# Artemis_Dionysus_Connectors.net
KiCad netlist of a schematic drawn in Altium Designer
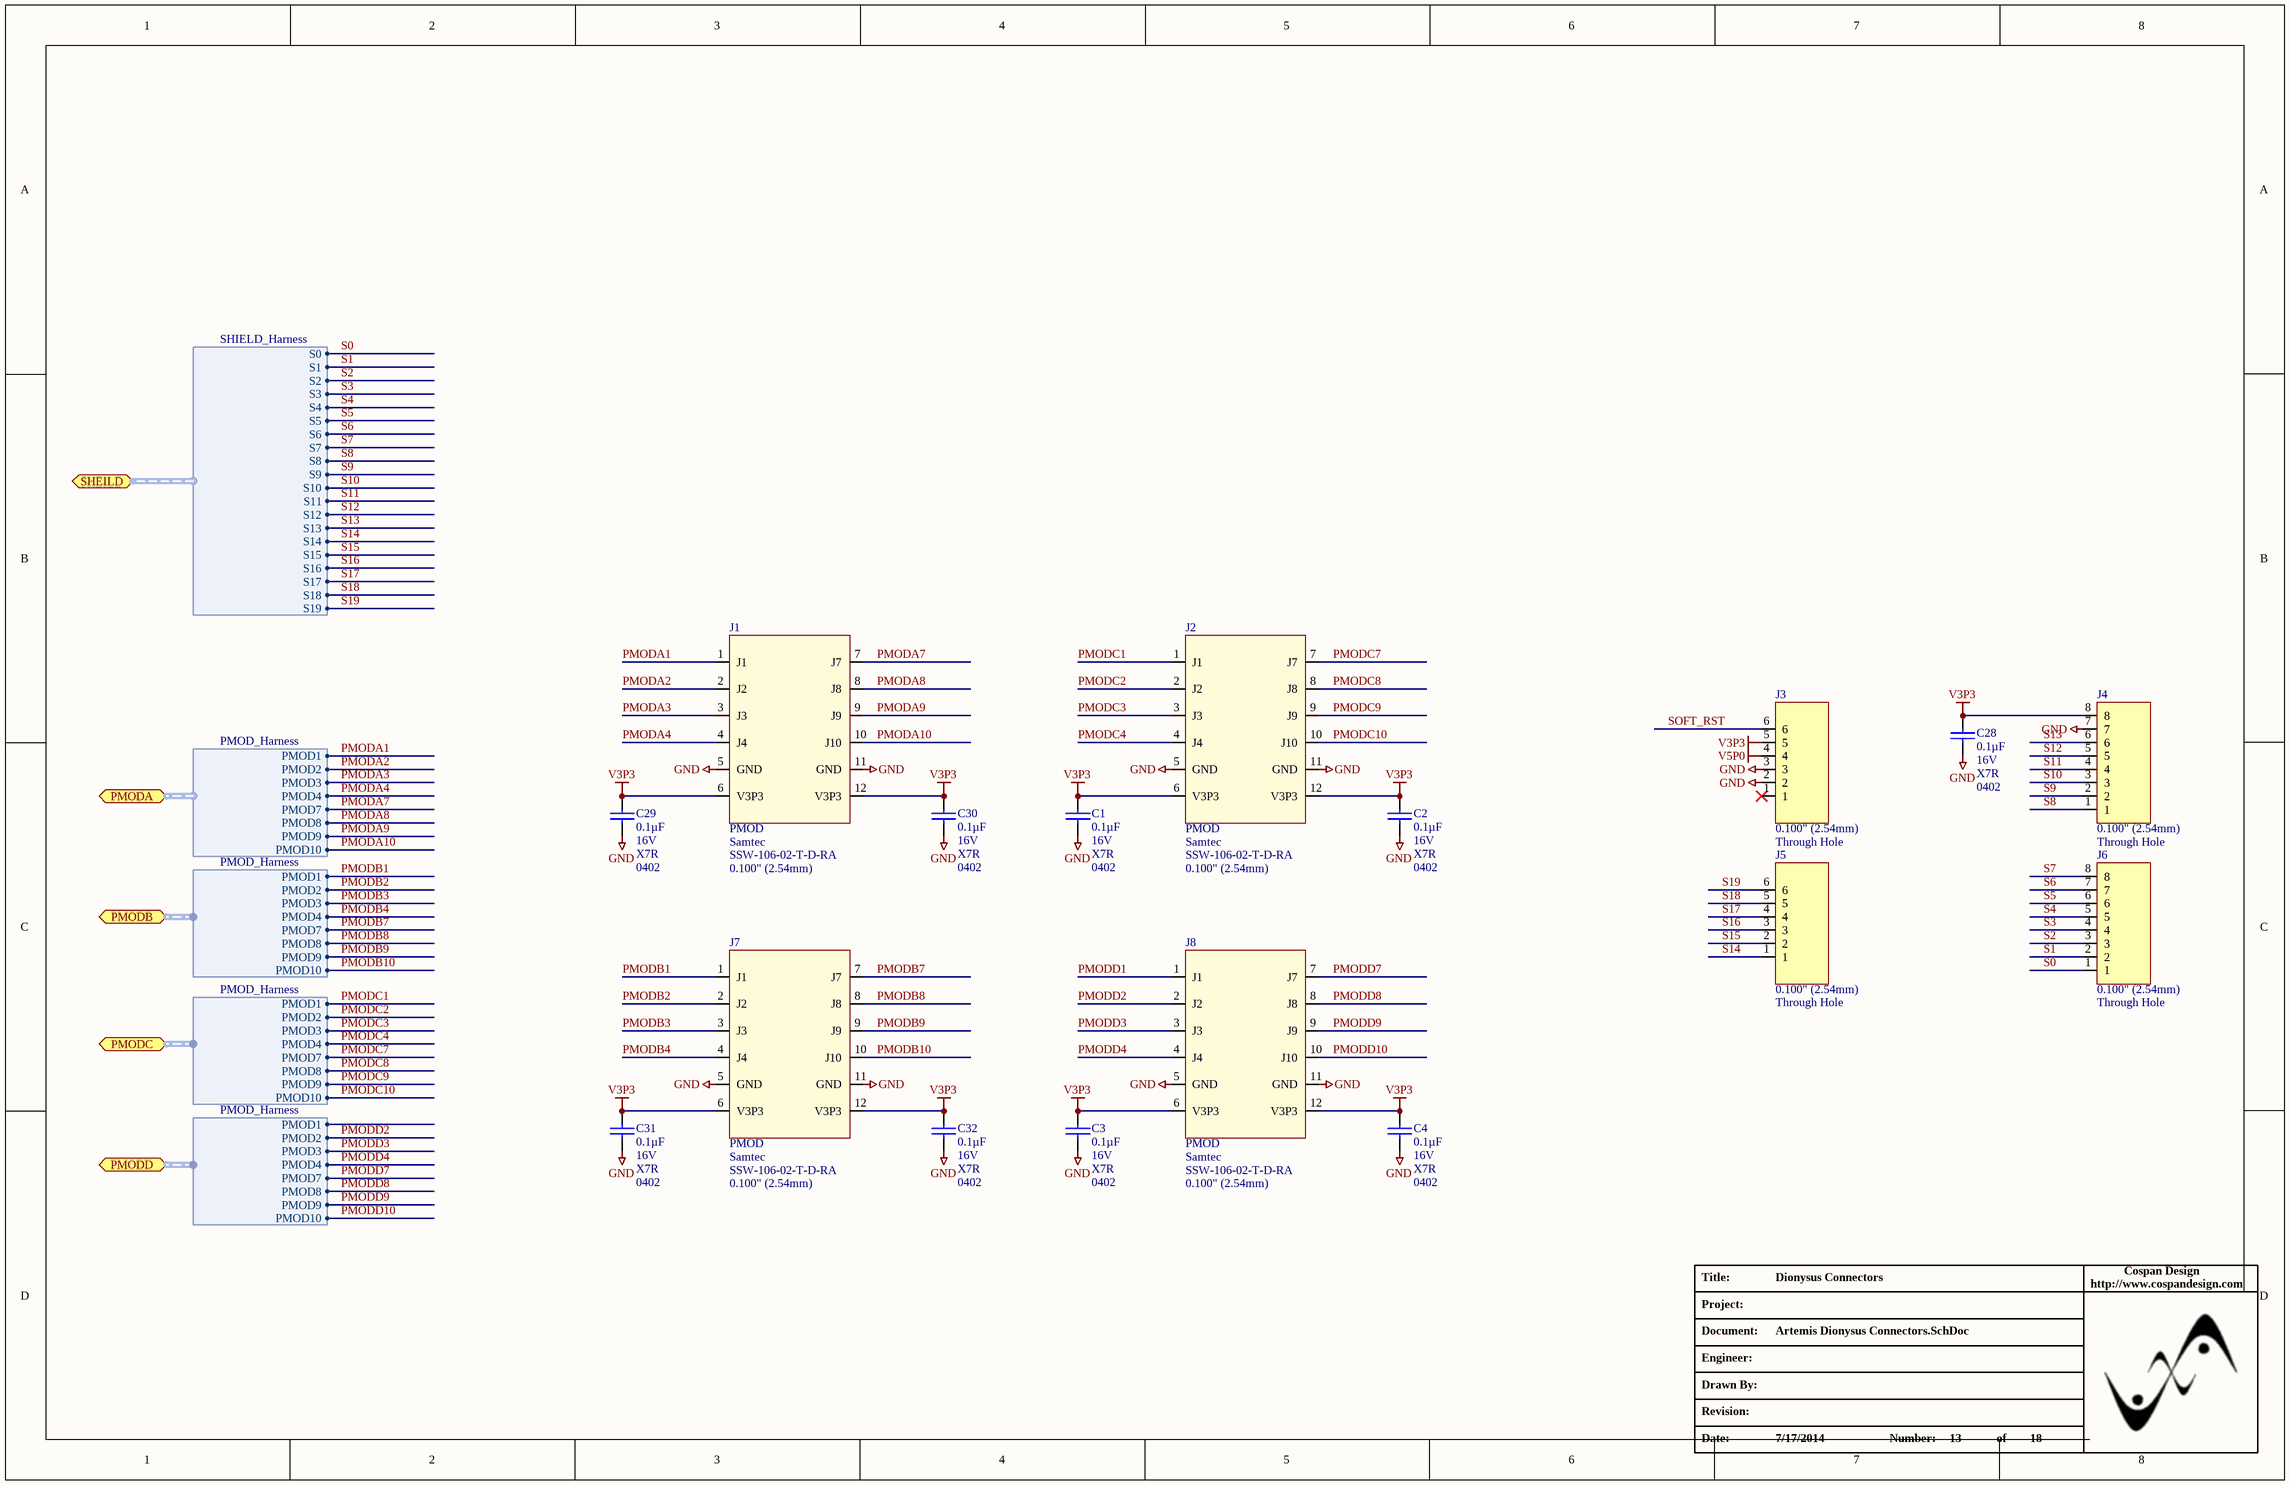
[diagram p0: Artemis Dionysus Connectors.SchDoc]

(export (version "E")
  (design (tool "Eeschema 10.0.6"))
  (components
    (comp (ref "C1")
      (value "0.1uF")
      (footprint "C_ERA-0402")
      (description "CAP CER .10UF 16V X7R 0402")
      (fields
        (field (name "MANUFACTURER") "TDK Corporation")
        (field (name "MANUFACTURER PART NUMBER") "C1005X7R1C104K")
        (field (name "CAPACITANCE") "0.1µF")
        (field (name "VOLTAGE - RATED") "16V")
        (field (name "TEMPERATURE COEFFICIENT") "X7R")
        (field (name "PACKAGE / CASE") "0402")
      )
      (libsource (lib "Main LibraryX") (part "C_0402_0.1UF_16V"))
    )
    (comp (ref "C2")
      (value "0.1uF")
      (footprint "C_ERA-0402")
      (description "CAP CER .10UF 16V X7R 0402")
      (fields
        (field (name "MANUFACTURER") "TDK Corporation")
        (field (name "MANUFACTURER PART NUMBER") "C1005X7R1C104K")
        (field (name "CAPACITANCE") "0.1µF")
        (field (name "VOLTAGE - RATED") "16V")
        (field (name "TEMPERATURE COEFFICIENT") "X7R")
        (field (name "PACKAGE / CASE") "0402")
      )
      (libsource (lib "Main LibraryX") (part "C_0402_0.1UF_16V"))
    )
    (comp (ref "C3")
      (value "0.1uF")
      (footprint "C_ERA-0402")
      (description "CAP CER .10UF 16V X7R 0402")
      (fields
        (field (name "MANUFACTURER") "TDK Corporation")
        (field (name "MANUFACTURER PART NUMBER") "C1005X7R1C104K")
        (field (name "CAPACITANCE") "0.1µF")
        (field (name "VOLTAGE - RATED") "16V")
        (field (name "TEMPERATURE COEFFICIENT") "X7R")
        (field (name "PACKAGE / CASE") "0402")
      )
      (libsource (lib "Main LibraryX") (part "C_0402_0.1UF_16V"))
    )
    (comp (ref "C4")
      (value "0.1uF")
      (footprint "C_ERA-0402")
      (description "CAP CER .10UF 16V X7R 0402")
      (fields
        (field (name "MANUFACTURER") "TDK Corporation")
        (field (name "MANUFACTURER PART NUMBER") "C1005X7R1C104K")
        (field (name "CAPACITANCE") "0.1µF")
        (field (name "VOLTAGE - RATED") "16V")
        (field (name "TEMPERATURE COEFFICIENT") "X7R")
        (field (name "PACKAGE / CASE") "0402")
      )
      (libsource (lib "Main LibraryX") (part "C_0402_0.1UF_16V"))
    )
    (comp (ref "C28")
      (value "0.1uF")
      (footprint "C_ERA-0402")
      (description "CAP CER .10UF 16V X7R 0402")
      (fields
        (field (name "MANUFACTURER") "TDK Corporation")
        (field (name "MANUFACTURER PART NUMBER") "C1005X7R1C104K")
        (field (name "CAPACITANCE") "0.1µF")
        (field (name "VOLTAGE - RATED") "16V")
        (field (name "TEMPERATURE COEFFICIENT") "X7R")
        (field (name "PACKAGE / CASE") "0402")
      )
      (libsource (lib "Main LibraryX") (part "C_0402_0.1UF_16V"))
    )
    (comp (ref "C29")
      (value "0.1uF")
      (footprint "C_ERA-0402")
      (description "CAP CER .10UF 16V X7R 0402")
      (fields
        (field (name "MANUFACTURER") "TDK Corporation")
        (field (name "MANUFACTURER PART NUMBER") "C1005X7R1C104K")
        (field (name "CAPACITANCE") "0.1µF")
        (field (name "VOLTAGE - RATED") "16V")
        (field (name "TEMPERATURE COEFFICIENT") "X7R")
        (field (name "PACKAGE / CASE") "0402")
      )
      (libsource (lib "Main LibraryX") (part "C_0402_0.1UF_16V"))
    )
    (comp (ref "C30")
      (value "0.1uF")
      (footprint "C_ERA-0402")
      (description "CAP CER .10UF 16V X7R 0402")
      (fields
        (field (name "MANUFACTURER") "TDK Corporation")
        (field (name "MANUFACTURER PART NUMBER") "C1005X7R1C104K")
        (field (name "CAPACITANCE") "0.1µF")
        (field (name "VOLTAGE - RATED") "16V")
        (field (name "TEMPERATURE COEFFICIENT") "X7R")
        (field (name "PACKAGE / CASE") "0402")
      )
      (libsource (lib "Main LibraryX") (part "C_0402_0.1UF_16V"))
    )
    (comp (ref "C31")
      (value "0.1uF")
      (footprint "C_ERA-0402")
      (description "CAP CER .10UF 16V X7R 0402")
      (fields
        (field (name "MANUFACTURER") "TDK Corporation")
        (field (name "MANUFACTURER PART NUMBER") "C1005X7R1C104K")
        (field (name "CAPACITANCE") "0.1µF")
        (field (name "VOLTAGE - RATED") "16V")
        (field (name "TEMPERATURE COEFFICIENT") "X7R")
        (field (name "PACKAGE / CASE") "0402")
      )
      (libsource (lib "Main LibraryX") (part "C_0402_0.1UF_16V"))
    )
    (comp (ref "C32")
      (value "0.1uF")
      (footprint "C_ERA-0402")
      (description "CAP CER .10UF 16V X7R 0402")
      (fields
        (field (name "MANUFACTURER") "TDK Corporation")
        (field (name "MANUFACTURER PART NUMBER") "C1005X7R1C104K")
        (field (name "CAPACITANCE") "0.1µF")
        (field (name "VOLTAGE - RATED") "16V")
        (field (name "TEMPERATURE COEFFICIENT") "X7R")
        (field (name "PACKAGE / CASE") "0402")
      )
      (libsource (lib "Main LibraryX") (part "C_0402_0.1UF_16V"))
    )
    (comp (ref "J1")
      (value "PMOD")
      (footprint "PMOD")
      (description "CONN FEMALE 12POS DL .1\" R/A TIN")
      (fields
        (field (name "MANUFACTURER") "Samtec")
        (field (name "MANUFACTURER PART NUMBER") "SSW-106-02-T-D-RA")
        (field (name "PITCH") "0.100\" (2.54mm)")
      )
      (libsource (lib "Main LibraryX") (part "J_PMOD"))
    )
    (comp (ref "J2")
      (value "PMOD")
      (footprint "PMOD")
      (description "CONN FEMALE 12POS DL .1\" R/A TIN")
      (fields
        (field (name "MANUFACTURER") "Samtec")
        (field (name "MANUFACTURER PART NUMBER") "SSW-106-02-T-D-RA")
        (field (name "PITCH") "0.100\" (2.54mm)")
      )
      (libsource (lib "Main LibraryX") (part "J_PMOD"))
    )
    (comp (ref "J3")
      (value "J_HDR1X6_THRHOLE_VERT_FEMALE")
      (footprint "HDR_1X6 - FEMALE")
      (description "CONN HEADER FEMALE 6POS .1\" TIN")
      (fields
        (field (name "MANUFACTURER") "Samtec")
        (field (name "MANUFACTURER PART NUMBER") "SSW-106-01-T-S")
        (field (name "PITCH") "0.100\" (2.54mm)")
        (field (name "MOUNTING TYPE") "Through Hole")
      )
      (libsource (lib "Main LibraryX") (part "J_HDR1X6_THRHOLE_VERT_FEMALE"))
    )
    (comp (ref "J4")
      (value "J_HDR1X8_THRHOLE_VERT_RECPT")
      (footprint "HDR_1X8 - FEMALE")
      (description "CONN HEADER FEMALE 8POS .1\" TIN")
      (fields
        (field (name "MANUFACTURER") "Samtec")
        (field (name "MANUFACTURER PART NUMBER") "SSW-108-01-T-S")
        (field (name "PITCH") "0.100\" (2.54mm)")
        (field (name "MOUNTING TYPE") "Through Hole")
      )
      (libsource (lib "Main LibraryX") (part "J_HDR1X8_THRHOLE_VERT_FEMALE"))
    )
    (comp (ref "J5")
      (value "J_HDR1X6_THRHOLE_VERT_FEMALE")
      (footprint "HDR_1X6 - FEMALE")
      (description "CONN HEADER FEMALE 6POS .1\" TIN")
      (fields
        (field (name "MANUFACTURER") "Samtec")
        (field (name "MANUFACTURER PART NUMBER") "SSW-106-01-T-S")
        (field (name "PITCH") "0.100\" (2.54mm)")
        (field (name "MOUNTING TYPE") "Through Hole")
      )
      (libsource (lib "Main LibraryX") (part "J_HDR1X6_THRHOLE_VERT_FEMALE"))
    )
    (comp (ref "J6")
      (value "J_HDR1X8_THRHOLE_VERT_RECPT")
      (footprint "HDR_1X8 - FEMALE")
      (description "CONN HEADER FEMALE 8POS .1\" TIN")
      (fields
        (field (name "MANUFACTURER") "Samtec")
        (field (name "MANUFACTURER PART NUMBER") "SSW-108-01-T-S")
        (field (name "PITCH") "0.100\" (2.54mm)")
        (field (name "MOUNTING TYPE") "Through Hole")
      )
      (libsource (lib "Main LibraryX") (part "J_HDR1X8_THRHOLE_VERT_FEMALE"))
    )
    (comp (ref "J7")
      (value "PMOD")
      (footprint "PMOD")
      (description "CONN FEMALE 12POS DL .1\" R/A TIN")
      (fields
        (field (name "MANUFACTURER") "Samtec")
        (field (name "MANUFACTURER PART NUMBER") "SSW-106-02-T-D-RA")
        (field (name "PITCH") "0.100\" (2.54mm)")
      )
      (libsource (lib "Main LibraryX") (part "J_PMOD"))
    )
    (comp (ref "J8")
      (value "PMOD")
      (footprint "PMOD")
      (description "CONN FEMALE 12POS DL .1\" R/A TIN")
      (fields
        (field (name "MANUFACTURER") "Samtec")
        (field (name "MANUFACTURER PART NUMBER") "SSW-106-02-T-D-RA")
        (field (name "PITCH") "0.100\" (2.54mm)")
      )
      (libsource (lib "Main LibraryX") (part "J_PMOD"))
    )
  )
  (nets
    (net (code "3") (name "/PMODA1") (class "Default")
      (node (ref "J1") (pin "1") (pinfunction "J1_1") (pintype "passive"))
    )
    (net (code "4") (name "/PMODA2") (class "Default")
      (node (ref "J1") (pin "2") (pinfunction "J2_2") (pintype "passive"))
    )
    (net (code "5") (name "/PMODA3") (class "Default")
      (node (ref "J1") (pin "3") (pinfunction "J3_3") (pintype "passive"))
    )
    (net (code "6") (name "/PMODA4") (class "Default")
      (node (ref "J1") (pin "4") (pinfunction "J4_4") (pintype "passive"))
    )
    (net (code "7") (name "/PMODA7") (class "Default")
      (node (ref "J1") (pin "7") (pinfunction "J7_7") (pintype "passive"))
    )
    (net (code "8") (name "/PMODA8") (class "Default")
      (node (ref "J1") (pin "8") (pinfunction "J8_8") (pintype "passive"))
    )
    (net (code "9") (name "/PMODA9") (class "Default")
      (node (ref "J1") (pin "9") (pinfunction "J9_9") (pintype "passive"))
    )
    (net (code "10") (name "/PMODA10") (class "Default")
      (node (ref "J1") (pin "10") (pinfunction "J10_10") (pintype "passive"))
    )
    (net (code "11") (name "/PMODB1") (class "Default")
      (node (ref "J7") (pin "1") (pinfunction "J1_1") (pintype "passive"))
    )
    (net (code "12") (name "/PMODB2") (class "Default")
      (node (ref "J7") (pin "2") (pinfunction "J2_2") (pintype "passive"))
    )
    (net (code "13") (name "/PMODB3") (class "Default")
      (node (ref "J7") (pin "3") (pinfunction "J3_3") (pintype "passive"))
    )
    (net (code "14") (name "/PMODB4") (class "Default")
      (node (ref "J7") (pin "4") (pinfunction "J4_4") (pintype "passive"))
    )
    (net (code "15") (name "/PMODB7") (class "Default")
      (node (ref "J7") (pin "7") (pinfunction "J7_7") (pintype "passive"))
    )
    (net (code "16") (name "/PMODB8") (class "Default")
      (node (ref "J7") (pin "8") (pinfunction "J8_8") (pintype "passive"))
    )
    (net (code "17") (name "/PMODB9") (class "Default")
      (node (ref "J7") (pin "9") (pinfunction "J9_9") (pintype "passive"))
    )
    (net (code "18") (name "/PMODB10") (class "Default")
      (node (ref "J7") (pin "10") (pinfunction "J10_10") (pintype "passive"))
    )
    (net (code "19") (name "/PMODC1") (class "Default")
      (node (ref "J2") (pin "1") (pinfunction "J1_1") (pintype "passive"))
    )
    (net (code "20") (name "/PMODC2") (class "Default")
      (node (ref "J2") (pin "2") (pinfunction "J2_2") (pintype "passive"))
    )
    (net (code "21") (name "/PMODC3") (class "Default")
      (node (ref "J2") (pin "3") (pinfunction "J3_3") (pintype "passive"))
    )
    (net (code "22") (name "/PMODC4") (class "Default")
      (node (ref "J2") (pin "4") (pinfunction "J4_4") (pintype "passive"))
    )
    (net (code "23") (name "/PMODC7") (class "Default")
      (node (ref "J2") (pin "7") (pinfunction "J7_7") (pintype "passive"))
    )
    (net (code "24") (name "/PMODC8") (class "Default")
      (node (ref "J2") (pin "8") (pinfunction "J8_8") (pintype "passive"))
    )
    (net (code "25") (name "/PMODC9") (class "Default")
      (node (ref "J2") (pin "9") (pinfunction "J9_9") (pintype "passive"))
    )
    (net (code "26") (name "/PMODC10") (class "Default")
      (node (ref "J2") (pin "10") (pinfunction "J10_10") (pintype "passive"))
    )
    (net (code "27") (name "/PMODD1") (class "Default")
      (node (ref "J8") (pin "1") (pinfunction "J1_1") (pintype "passive"))
    )
    (net (code "28") (name "/PMODD2") (class "Default")
      (node (ref "J8") (pin "2") (pinfunction "J2_2") (pintype "passive"))
    )
    (net (code "29") (name "/PMODD3") (class "Default")
      (node (ref "J8") (pin "3") (pinfunction "J3_3") (pintype "passive"))
    )
    (net (code "30") (name "/PMODD4") (class "Default")
      (node (ref "J8") (pin "4") (pinfunction "J4_4") (pintype "passive"))
    )
    (net (code "31") (name "/PMODD7") (class "Default")
      (node (ref "J8") (pin "7") (pinfunction "J7_7") (pintype "passive"))
    )
    (net (code "32") (name "/PMODD8") (class "Default")
      (node (ref "J8") (pin "8") (pinfunction "J8_8") (pintype "passive"))
    )
    (net (code "33") (name "/PMODD9") (class "Default")
      (node (ref "J8") (pin "9") (pinfunction "J9_9") (pintype "passive"))
    )
    (net (code "34") (name "/PMODD10") (class "Default")
      (node (ref "J8") (pin "10") (pinfunction "J10_10") (pintype "passive"))
    )
    (net (code "35") (name "/S0") (class "Default")
      (node (ref "J6") (pin "1") (pinfunction "1_1") (pintype "passive"))
    )
    (net (code "36") (name "/S1") (class "Default")
      (node (ref "J6") (pin "2") (pinfunction "2_2") (pintype "passive"))
    )
    (net (code "37") (name "/S2") (class "Default")
      (node (ref "J6") (pin "3") (pinfunction "3_3") (pintype "passive"))
    )
    (net (code "38") (name "/S3") (class "Default")
      (node (ref "J6") (pin "4") (pinfunction "4_4") (pintype "passive"))
    )
    (net (code "39") (name "/S4") (class "Default")
      (node (ref "J6") (pin "5") (pinfunction "5_5") (pintype "passive"))
    )
    (net (code "40") (name "/S5") (class "Default")
      (node (ref "J6") (pin "6") (pinfunction "6_6") (pintype "passive"))
    )
    (net (code "41") (name "/S6") (class "Default")
      (node (ref "J6") (pin "7") (pinfunction "7_7") (pintype "passive"))
    )
    (net (code "42") (name "/S7") (class "Default")
      (node (ref "J6") (pin "8") (pinfunction "8_8") (pintype "passive"))
    )
    (net (code "43") (name "/S8") (class "Default")
      (node (ref "J4") (pin "1") (pinfunction "1_1") (pintype "passive"))
    )
    (net (code "44") (name "/S9") (class "Default")
      (node (ref "J4") (pin "2") (pinfunction "2_2") (pintype "passive"))
    )
    (net (code "45") (name "/S10") (class "Default")
      (node (ref "J4") (pin "3") (pinfunction "3_3") (pintype "passive"))
    )
    (net (code "46") (name "/S11") (class "Default")
      (node (ref "J4") (pin "4") (pinfunction "4_4") (pintype "passive"))
    )
    (net (code "47") (name "/S12") (class "Default")
      (node (ref "J4") (pin "5") (pinfunction "5_5") (pintype "passive"))
    )
    (net (code "48") (name "/S13") (class "Default")
      (node (ref "J4") (pin "6") (pinfunction "6_6") (pintype "passive"))
    )
    (net (code "49") (name "/S14") (class "Default")
      (node (ref "J5") (pin "1") (pinfunction "1_1") (pintype "passive"))
    )
    (net (code "50") (name "/S15") (class "Default")
      (node (ref "J5") (pin "2") (pinfunction "2_2") (pintype "passive"))
    )
    (net (code "51") (name "/S16") (class "Default")
      (node (ref "J5") (pin "3") (pinfunction "3_3") (pintype "passive"))
    )
    (net (code "52") (name "/S17") (class "Default")
      (node (ref "J5") (pin "4") (pinfunction "4_4") (pintype "passive"))
    )
    (net (code "53") (name "/S18") (class "Default")
      (node (ref "J5") (pin "5") (pinfunction "5_5") (pintype "passive"))
    )
    (net (code "54") (name "/S19") (class "Default")
      (node (ref "J5") (pin "6") (pinfunction "6_6") (pintype "passive"))
    )
    (net (code "55") (name "/SOFT_RST") (class "Default")
      (node (ref "J3") (pin "6") (pinfunction "6_6") (pintype "passive"))
    )
    (net (code "58") (name "GND") (class "Default")
      (node (ref "C1") (pin "1") (pinfunction "1_1") (pintype "passive"))
      (node (ref "C2") (pin "1") (pinfunction "1_1") (pintype "passive"))
      (node (ref "C28") (pin "1") (pinfunction "1_1") (pintype "passive"))
      (node (ref "C29") (pin "1") (pinfunction "1_1") (pintype "passive"))
      (node (ref "C3") (pin "1") (pinfunction "1_1") (pintype "passive"))
      (node (ref "C30") (pin "1") (pinfunction "1_1") (pintype "passive"))
      (node (ref "C31") (pin "1") (pinfunction "1_1") (pintype "passive"))
      (node (ref "C32") (pin "1") (pinfunction "1_1") (pintype "passive"))
      (node (ref "C4") (pin "1") (pinfunction "1_1") (pintype "passive"))
      (node (ref "J1") (pin "11") (pinfunction "GND_11") (pintype "passive"))
      (node (ref "J1") (pin "5") (pinfunction "GND_5") (pintype "passive"))
      (node (ref "J2") (pin "11") (pinfunction "GND_11") (pintype "passive"))
      (node (ref "J2") (pin "5") (pinfunction "GND_5") (pintype "passive"))
      (node (ref "J3") (pin "2") (pinfunction "2_2") (pintype "passive"))
      (node (ref "J3") (pin "3") (pinfunction "3_3") (pintype "passive"))
      (node (ref "J4") (pin "7") (pinfunction "7_7") (pintype "passive"))
      (node (ref "J7") (pin "11") (pinfunction "GND_11") (pintype "passive"))
      (node (ref "J7") (pin "5") (pinfunction "GND_5") (pintype "passive"))
      (node (ref "J8") (pin "11") (pinfunction "GND_11") (pintype "passive"))
      (node (ref "J8") (pin "5") (pinfunction "GND_5") (pintype "passive"))
    )
    (net (code "59") (name "V3P3") (class "Default")
      (node (ref "C1") (pin "2") (pinfunction "2_2") (pintype "passive"))
      (node (ref "C2") (pin "2") (pinfunction "2_2") (pintype "passive"))
      (node (ref "C28") (pin "2") (pinfunction "2_2") (pintype "passive"))
      (node (ref "C29") (pin "2") (pinfunction "2_2") (pintype "passive"))
      (node (ref "C3") (pin "2") (pinfunction "2_2") (pintype "passive"))
      (node (ref "C30") (pin "2") (pinfunction "2_2") (pintype "passive"))
      (node (ref "C31") (pin "2") (pinfunction "2_2") (pintype "passive"))
      (node (ref "C32") (pin "2") (pinfunction "2_2") (pintype "passive"))
      (node (ref "C4") (pin "2") (pinfunction "2_2") (pintype "passive"))
      (node (ref "J1") (pin "12") (pinfunction "V3P3_12") (pintype "passive"))
      (node (ref "J1") (pin "6") (pinfunction "V3P3_6") (pintype "passive"))
      (node (ref "J2") (pin "12") (pinfunction "V3P3_12") (pintype "passive"))
      (node (ref "J2") (pin "6") (pinfunction "V3P3_6") (pintype "passive"))
      (node (ref "J3") (pin "5") (pinfunction "5_5") (pintype "passive"))
      (node (ref "J4") (pin "8") (pinfunction "8_8") (pintype "passive"))
      (node (ref "J7") (pin "12") (pinfunction "V3P3_12") (pintype "passive"))
      (node (ref "J7") (pin "6") (pinfunction "V3P3_6") (pintype "passive"))
      (node (ref "J8") (pin "12") (pinfunction "V3P3_12") (pintype "passive"))
      (node (ref "J8") (pin "6") (pinfunction "V3P3_6") (pintype "passive"))
    )
    (net (code "60") (name "V5P0") (class "Default")
      (node (ref "J3") (pin "4") (pinfunction "4_4") (pintype "passive"))
    )
    (net (code "61") (name "unconnected-(J3-Pad1)") (class "Default")
      (node (ref "J3") (pin "1") (pinfunction "1_1") (pintype "passive+no_connect"))
    )
  )
)
